# PS2.net
KiCad netlist of a schematic drawn in Altium Designer
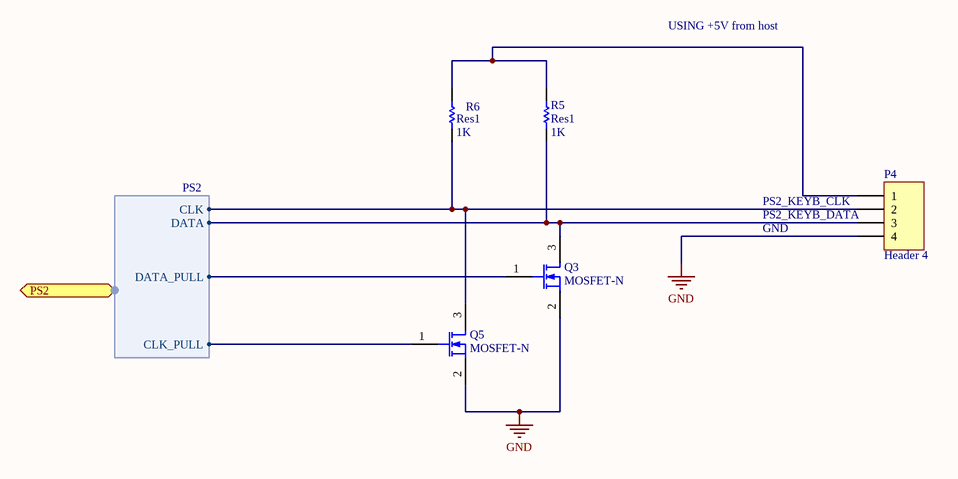
[diagram p0: PS2.SchDoc]

(export (version "E")
  (design (tool "Eeschema 10.0.6"))
  (components
    (comp (ref "P4")
      (value "Header 4")
      (footprint "S04B-PASK-2")
      (description "Header, 4-Pin")
      (fields (field (name "PUBLISHER") "Altium Limited"))
      (libsource (lib "Miscellaneous Connectors") (part "Header 4"))
    )
    (comp (ref "Q3")
      (value "MOSFET-N")
      (footprint "2N7002")
      (description "N-Channel MOSFET")
      (fields (field (name "PUBLISHER") "Altium Limited"))
      (libsource (lib "Miscellaneous Devices") (part "MOSFET-N"))
    )
    (comp (ref "Q5")
      (value "MOSFET-N")
      (footprint "2N7002")
      (description "N-Channel MOSFET")
      (fields (field (name "PUBLISHER") "Altium Limited"))
      (libsource (lib "Miscellaneous Devices") (part "MOSFET-N"))
    )
    (comp (ref "R5")
      (value "Res1")
      (footprint "R0603")
      (description "Resistor")
      (fields (field (name "ALTIUM_VALUE") "1K") (field (name "PUBLISHER") "Altium Limited"))
      (libsource (lib "Miscellaneous Devices") (part "Res1"))
    )
    (comp (ref "R6")
      (value "Res1")
      (footprint "R0603")
      (description "Resistor")
      (fields (field (name "ALTIUM_VALUE") "1K") (field (name "PUBLISHER") "Altium Limited"))
      (libsource (lib "Miscellaneous Devices") (part "Res1"))
    )
  )
  (nets
    (net (code "2") (name "/CLK") (class "Default")
      (node (ref "P4") (pin "2") (pinfunction "2_2") (pintype "passive"))
      (node (ref "Q5") (pin "3") (pinfunction "D_3") (pintype "passive"))
      (node (ref "R6") (pin "1") (pinfunction "1_1") (pintype "passive"))
    )
    (net (code "3") (name "/CLK_PULL") (class "Default")
      (node (ref "Q5") (pin "1") (pinfunction "G_1") (pintype "passive"))
    )
    (net (code "4") (name "/DATA") (class "Default")
      (node (ref "P4") (pin "3") (pinfunction "3_3") (pintype "passive"))
      (node (ref "Q3") (pin "3") (pinfunction "D_3") (pintype "passive"))
      (node (ref "R5") (pin "1") (pinfunction "1_1") (pintype "passive"))
    )
    (net (code "5") (name "/DATA_PULL") (class "Default")
      (node (ref "Q3") (pin "1") (pinfunction "G_1") (pintype "passive"))
    )
    (net (code "7") (name "GND") (class "Default")
      (node (ref "P4") (pin "4") (pinfunction "4_4") (pintype "passive"))
      (node (ref "Q3") (pin "2") (pinfunction "S_2") (pintype "passive"))
      (node (ref "Q5") (pin "2") (pinfunction "S_2") (pintype "passive"))
    )
    (net (code "8") (name "Net-(P4-Pad1)") (class "Default")
      (node (ref "P4") (pin "1") (pinfunction "1_1") (pintype "passive"))
      (node (ref "R5") (pin "2") (pinfunction "2_2") (pintype "passive"))
      (node (ref "R6") (pin "2") (pinfunction "2_2") (pintype "passive"))
    )
  )
)
